# Tortoise_Board_schematic.net
KiCad netlist of a schematic drawn in EasyEDA
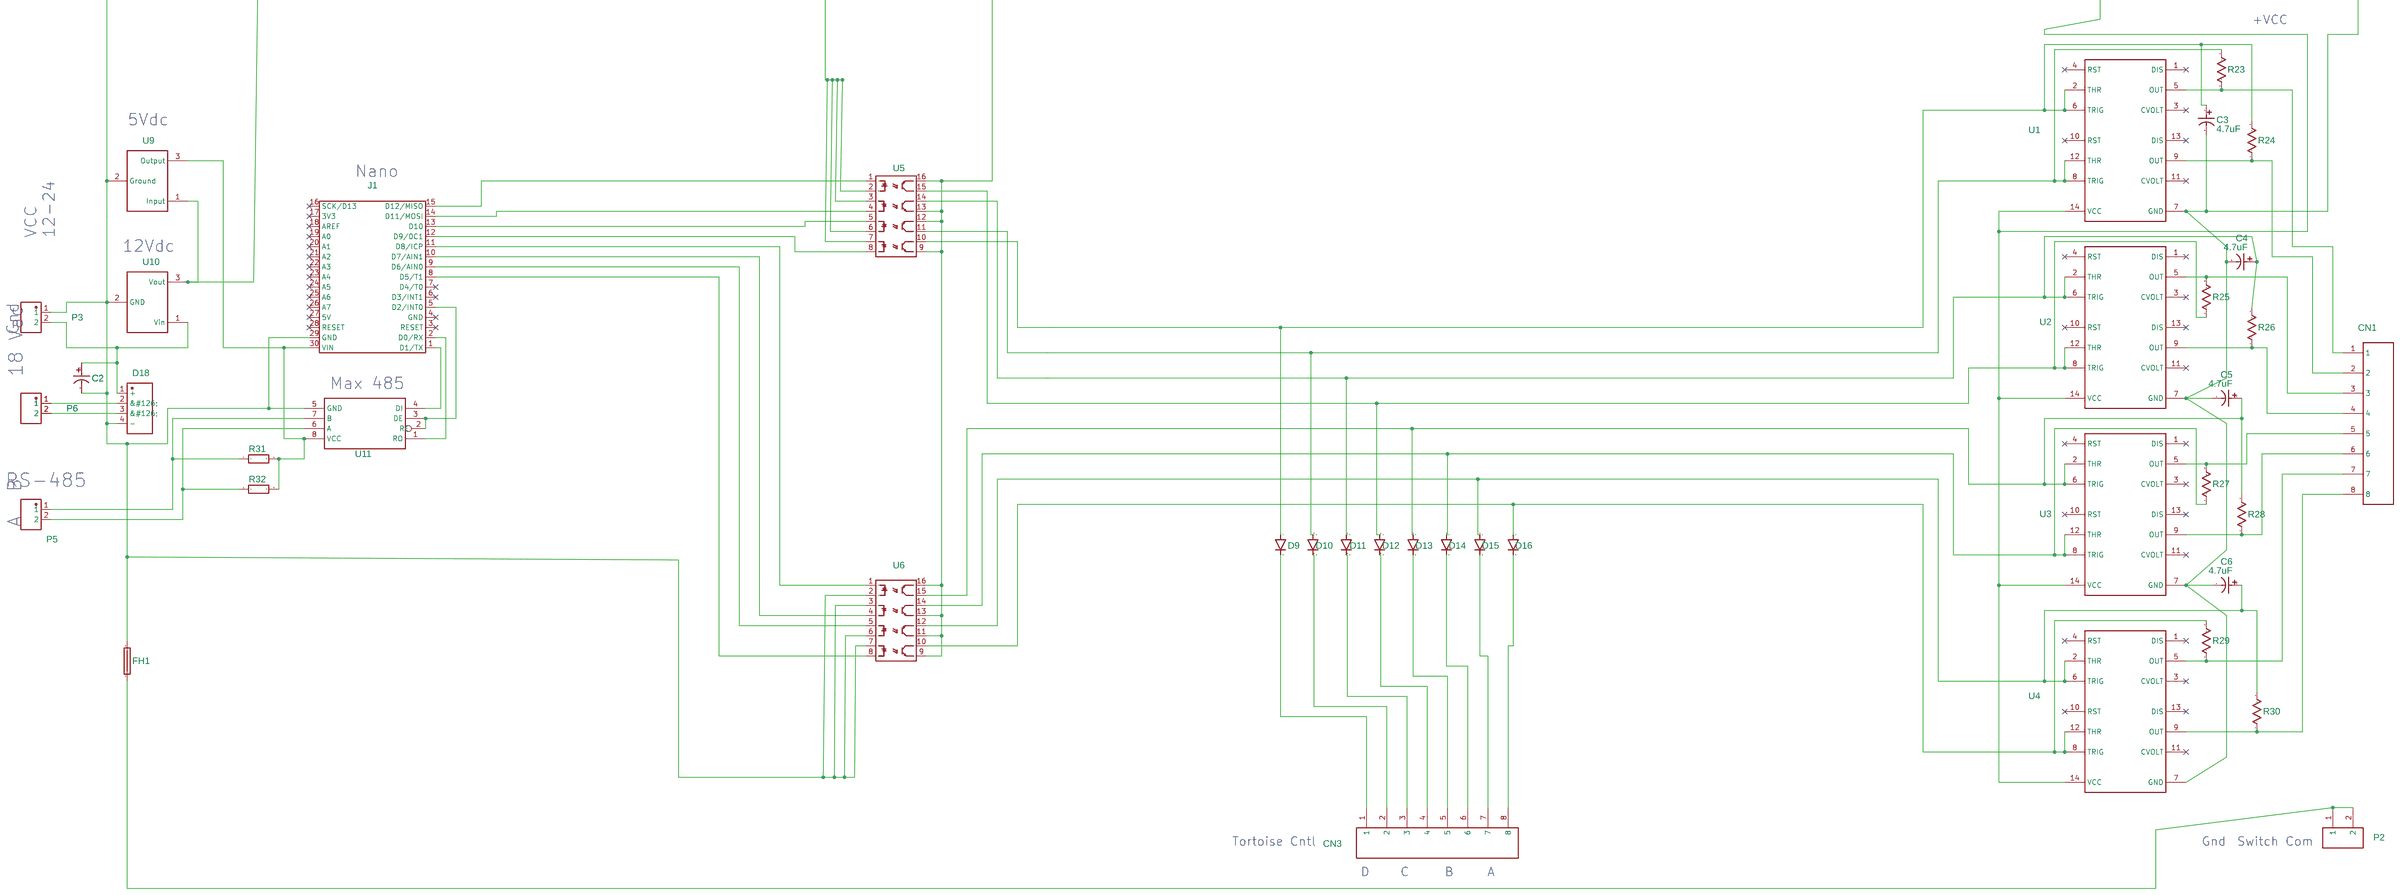
[diagram p0: schematic sheet]

(export (version "E")
  (design (tool "Eeschema 10.0.6"))
  (components
    (comp (ref "C2")
      (value "470uF")
      (fields
        (field (name "BOM_Manufacturer Part") "470uF 100V 16*25")
        (field (name "BOM_Supplier Part") "C72551")
      )
      (libsource (lib "") (part "470uF 100V 16*25"))
    )
    (comp (ref "C3")
      (value "4.7uF")
      (fields
        (field (name "BOM_Manufacturer Part") "4.7uF 50V 4*7")
        (field (name "BOM_Supplier Part") "C43841")
      )
      (libsource (lib "") (part "4.7uF 50V 4*7_1"))
    )
    (comp (ref "C4")
      (value "4.7uF")
      (fields
        (field (name "BOM_Manufacturer Part") "4.7uF 50V 4*7")
        (field (name "BOM_Supplier Part") "C43841")
      )
      (libsource (lib "") (part "4.7uF 50V 4*7"))
    )
    (comp (ref "C5")
      (value "4.7uF")
      (fields
        (field (name "BOM_Manufacturer Part") "4.7uF 50V 4*7")
        (field (name "BOM_Supplier Part") "C43841")
      )
      (libsource (lib "") (part "4.7uF 50V 4*7"))
    )
    (comp (ref "C6")
      (value "4.7uF")
      (fields
        (field (name "BOM_Manufacturer Part") "4.7uF 50V 4*7")
        (field (name "BOM_Supplier Part") "C43841")
      )
      (libsource (lib "") (part "4.7uF 50V 4*7"))
    )
    (comp (ref "CN1")
      (value "WJ25C-B-7.62-8P-13-00A")
      (fields (field (name "BOM_Supplier Part") "C49492"))
      (libsource (lib "") (part "Unknown_1845_850"))
    )
    (comp (ref "CN3")
      (value "WJ25C-B-7.62-8P-13-00A")
      (fields (field (name "BOM_Supplier Part") "C49492"))
      (libsource (lib "") (part "Unknown_930_1250"))
    )
    (comp (ref "D9")
      (value "DIODE")
      (fields (field (name "BOM_Manufacturer Part") "?"))
      (libsource (lib "") (part "Unknown_775_970"))
    )
    (comp (ref "D10")
      (value "DIODE")
      (fields (field (name "BOM_Manufacturer Part") "?"))
      (libsource (lib "") (part "Unknown_808_970"))
    )
    (comp (ref "D11")
      (value "DIODE")
      (fields (field (name "BOM_Manufacturer Part") "?"))
      (libsource (lib "") (part "Unknown_841_970"))
    )
    (comp (ref "D12")
      (value "DIODE")
      (fields (field (name "BOM_Manufacturer Part") "?"))
      (libsource (lib "") (part "Unknown_874_970"))
    )
    (comp (ref "D13")
      (value "DIODE")
      (fields (field (name "BOM_Manufacturer Part") "?"))
      (libsource (lib "") (part "Unknown_906_970"))
    )
    (comp (ref "D14")
      (value "DIODE")
      (fields (field (name "BOM_Manufacturer Part") "?"))
      (libsource (lib "") (part "Unknown_939_970"))
    )
    (comp (ref "D15")
      (value "DIODE")
      (fields (field (name "BOM_Manufacturer Part") "?"))
      (libsource (lib "") (part "Unknown_972_970"))
    )
    (comp (ref "D16")
      (value "DIODE")
      (fields (field (name "BOM_Manufacturer Part") "?"))
      (libsource (lib "") (part "Unknown_1005_970"))
    )
    (comp (ref "D18")
      (value "D50SB100")
      (fields (field (name "BOM_Supplier Part") "C411148"))
      (libsource (lib "") (part "Unknown_-360_835"))
    )
    (comp (ref "FH1")
      (value "64600001003")
      (fields (field (name "BOM_Supplier Part") "C206887"))
      (libsource (lib "") (part "Unknown_-365_1085"))
    )
    (comp (ref "J1") (value "Arduino_Nano_Header") (libsource (lib "") (part "Unknown_-125_705")))
    (comp (ref "P2")
      (value "WJ762-7.62-2P-13-00A")
      (fields (field (name "BOM_Supplier Part") "C72333"))
      (libsource (lib "") (part "Unknown_1825_1250"))
    )
    (comp (ref "P3")
      (value "WJ25C-B-2P")
      (fields (field (name "BOM_Supplier Part") "C8422"))
      (libsource (lib "") (part "Unknown_-460_745"))
    )
    (comp (ref "P5")
      (value "WJ25C-B-2P")
      (fields (field (name "BOM_Supplier Part") "C8422"))
      (libsource (lib "") (part "Unknown_-460_940"))
    )
    (comp (ref "P6")
      (value "WJ25C-B-2P")
      (fields (field (name "BOM_Supplier Part") "C8422"))
      (libsource (lib "") (part "Unknown_-460_835"))
    )
    (comp (ref "R23")
      (value "10k")
      (fields
        (field (name "BOM_Manufacturer Part") "RESISTOR_ALONG")
        (field (name "BOM_Supplier Part") "9339116")
      )
      (libsource (lib "") (part "Unknown_1705_500"))
    )
    (comp (ref "R24")
      (value "10k")
      (fields
        (field (name "BOM_Manufacturer Part") "RESISTOR_ALONG")
        (field (name "BOM_Supplier Part") "9339116")
      )
      (libsource (lib "") (part "Unknown_1735_570"))
    )
    (comp (ref "R25")
      (value "10k")
      (fields
        (field (name "BOM_Manufacturer Part") "RESISTOR_ALONG")
        (field (name "BOM_Supplier Part") "9339116")
      )
      (libsource (lib "") (part "Unknown_1690_725"))
    )
    (comp (ref "R26")
      (value "10k")
      (fields
        (field (name "BOM_Manufacturer Part") "RESISTOR_ALONG")
        (field (name "BOM_Supplier Part") "9339116")
      )
      (libsource (lib "") (part "Unknown_1735_755"))
    )
    (comp (ref "R27")
      (value "10k")
      (fields
        (field (name "BOM_Manufacturer Part") "RESISTOR_ALONG")
        (field (name "BOM_Supplier Part") "9339116")
      )
      (libsource (lib "") (part "Unknown_1690_910"))
    )
    (comp (ref "R28")
      (value "10k")
      (fields
        (field (name "BOM_Manufacturer Part") "RESISTOR_ALONG")
        (field (name "BOM_Supplier Part") "9339116")
      )
      (libsource (lib "") (part "Unknown_1725_940"))
    )
    (comp (ref "R29")
      (value "10k")
      (fields
        (field (name "BOM_Manufacturer Part") "RESISTOR_ALONG")
        (field (name "BOM_Supplier Part") "9339116")
      )
      (libsource (lib "") (part "Unknown_1690_1065"))
    )
    (comp (ref "R30")
      (value "10k")
      (fields
        (field (name "BOM_Manufacturer Part") "RESISTOR_ALONG")
        (field (name "BOM_Supplier Part") "9339116")
      )
      (libsource (lib "") (part "Unknown_1740_1135"))
    )
    (comp (ref "R31")
      (value "10K")
      (fields
        (field (name "BOM_Manufacturer Part") "CFR0W4J0103A50")
        (field (name "BOM_Supplier Part") "C61299")
      )
      (libsource (lib "") (part "CFR0W4J0103A50"))
    )
    (comp (ref "R32")
      (value "10K")
      (fields
        (field (name "BOM_Manufacturer Part") "CFR0W4J0103A50")
        (field (name "BOM_Supplier Part") "C61299")
      )
      (libsource (lib "") (part "CFR0W4J0103A50"))
    )
    (comp (ref "U1")
      (value "LM556CN")
      (fields (field (name "BOM_Manufacturer Part") "?"))
      (libsource (lib "") (part "Unknown_1610_570"))
    )
    (comp (ref "U2")
      (value "LM556CN")
      (fields (field (name "BOM_Manufacturer Part") "?"))
      (libsource (lib "") (part "Unknown_1610_755"))
    )
    (comp (ref "U3")
      (value "LM556CN")
      (fields (field (name "BOM_Manufacturer Part") "?"))
      (libsource (lib "") (part "Unknown_1610_940"))
    )
    (comp (ref "U4")
      (value "LM556CN")
      (fields (field (name "BOM_Manufacturer Part") "?"))
      (libsource (lib "") (part "Unknown_1610_1135"))
    )
    (comp (ref "U5")
      (value "Optocoupler_ILQ74 QUAD")
      (fields (field (name "BOM_Manufacturer Part") "?"))
      (libsource (lib "") (part "Unknown_395_645"))
    )
    (comp (ref "U6")
      (value "Optocoupler_ILQ74 QUAD")
      (fields (field (name "BOM_Manufacturer Part") "?"))
      (libsource (lib "") (part "Unknown_395_1045"))
    )
    (comp (ref "U9")
      (value "MC7805BTG")
      (fields (field (name "BOM_Supplier Part") "C45385"))
      (libsource (lib "") (part "Unknown_-345_610"))
    )
    (comp (ref "U10")
      (value "CJ7812")
      (fields (field (name "BOM_Supplier Part") "C77894"))
      (libsource (lib "") (part "Unknown_-345_730"))
    )
    (comp (ref "U11") (value "MAX485DIL") (libsource (lib "") (part "Unknown_-130_850")))
  )
  (nets
    (net (code "1") (name "Net-(C3-Pad1)") (class "Default")
      (node (ref "C3") (pin "1") (pinfunction "1_1") (pintype "input"))
      (node (ref "D9") (pin "A") (pinfunction "A_A") (pintype "unspecified"))
      (node (ref "R24") (pin "2") (pinfunction "2_2") (pintype "unspecified"))
      (node (ref "U1") (pin "2") (pinfunction "THR_2") (pintype "unspecified"))
      (node (ref "U1") (pin "6") (pinfunction "TRIG_6") (pintype "unspecified"))
      (node (ref "U5") (pin "10") (pinfunction "10_10") (pintype "unspecified"))
    )
    (net (code "2") (name "Net-(C4-Pad1)") (class "Default")
      (node (ref "C4") (pin "1") (pinfunction "1_1") (pintype "input"))
      (node (ref "D11") (pin "A") (pinfunction "A_A") (pintype "unspecified"))
      (node (ref "R26") (pin "2") (pinfunction "2_2") (pintype "unspecified"))
      (node (ref "U2") (pin "2") (pinfunction "THR_2") (pintype "unspecified"))
      (node (ref "U2") (pin "6") (pinfunction "TRIG_6") (pintype "unspecified"))
      (node (ref "U5") (pin "14") (pinfunction "14_14") (pintype "unspecified"))
    )
    (net (code "3") (name "Net-(C5-Pad1)") (class "Default")
      (node (ref "C5") (pin "1") (pinfunction "1_1") (pintype "input"))
      (node (ref "D13") (pin "A") (pinfunction "A_A") (pintype "unspecified"))
      (node (ref "R28") (pin "2") (pinfunction "2_2") (pintype "unspecified"))
      (node (ref "U3") (pin "2") (pinfunction "THR_2") (pintype "unspecified"))
      (node (ref "U3") (pin "6") (pinfunction "TRIG_6") (pintype "unspecified"))
      (node (ref "U6") (pin "15") (pinfunction "15_15") (pintype "unspecified"))
    )
    (net (code "4") (name "Net-(C6-Pad1)") (class "Default")
      (node (ref "C6") (pin "1") (pinfunction "1_1") (pintype "input"))
      (node (ref "D15") (pin "A") (pinfunction "A_A") (pintype "unspecified"))
      (node (ref "R30") (pin "2") (pinfunction "2_2") (pintype "unspecified"))
      (node (ref "U4") (pin "2") (pinfunction "THR_2") (pintype "unspecified"))
      (node (ref "U4") (pin "6") (pinfunction "TRIG_6") (pintype "unspecified"))
      (node (ref "U6") (pin "12") (pinfunction "12_12") (pintype "unspecified"))
    )
    (net (code "5") (name "Net-(CN1-Pad1)") (class "Default")
      (node (ref "CN1") (pin "1") (pinfunction "1_1") (pintype "input"))
      (node (ref "R23") (pin "1") (pinfunction "1_1") (pintype "unspecified"))
      (node (ref "U1") (pin "5") (pinfunction "OUT_5") (pintype "output"))
    )
    (net (code "6") (name "Net-(CN1-Pad2)") (class "Default")
      (node (ref "CN1") (pin "2") (pinfunction "2_2") (pintype "input"))
      (node (ref "R24") (pin "1") (pinfunction "1_1") (pintype "unspecified"))
      (node (ref "U1") (pin "9") (pinfunction "OUT_9") (pintype "output"))
    )
    (net (code "7") (name "Net-(CN1-Pad3)") (class "Default")
      (node (ref "CN1") (pin "3") (pinfunction "3_3") (pintype "input"))
      (node (ref "R25") (pin "2") (pinfunction "2_2") (pintype "unspecified"))
      (node (ref "U2") (pin "5") (pinfunction "OUT_5") (pintype "output"))
    )
    (net (code "8") (name "Net-(CN1-Pad4)") (class "Default")
      (node (ref "CN1") (pin "4") (pinfunction "4_4") (pintype "input"))
      (node (ref "R26") (pin "1") (pinfunction "1_1") (pintype "unspecified"))
      (node (ref "U2") (pin "9") (pinfunction "OUT_9") (pintype "output"))
    )
    (net (code "9") (name "Net-(CN1-Pad5)") (class "Default")
      (node (ref "CN1") (pin "5") (pinfunction "5_5") (pintype "input"))
      (node (ref "R27") (pin "2") (pinfunction "2_2") (pintype "unspecified"))
      (node (ref "U3") (pin "5") (pinfunction "OUT_5") (pintype "output"))
    )
    (net (code "10") (name "Net-(CN1-Pad6)") (class "Default")
      (node (ref "CN1") (pin "6") (pinfunction "6_6") (pintype "input"))
      (node (ref "R28") (pin "1") (pinfunction "1_1") (pintype "unspecified"))
      (node (ref "U3") (pin "9") (pinfunction "OUT_9") (pintype "output"))
    )
    (net (code "11") (name "Net-(CN1-Pad7)") (class "Default")
      (node (ref "CN1") (pin "7") (pinfunction "7_7") (pintype "input"))
      (node (ref "R29") (pin "1") (pinfunction "1_1") (pintype "unspecified"))
      (node (ref "U4") (pin "5") (pinfunction "OUT_5") (pintype "output"))
    )
    (net (code "12") (name "Net-(CN1-Pad8)") (class "Default")
      (node (ref "CN1") (pin "8") (pinfunction "8_8") (pintype "input"))
      (node (ref "R30") (pin "1") (pinfunction "1_1") (pintype "unspecified"))
      (node (ref "U4") (pin "9") (pinfunction "OUT_9") (pintype "output"))
    )
    (net (code "13") (name "Net-(CN3-Pad1)") (class "Default")
      (node (ref "CN3") (pin "1") (pinfunction "1_1") (pintype "input"))
      (node (ref "D9") (pin "C") (pinfunction "C_C") (pintype "unspecified"))
    )
    (net (code "14") (name "Net-(CN3-Pad2)") (class "Default")
      (node (ref "CN3") (pin "2") (pinfunction "2_2") (pintype "input"))
      (node (ref "D10") (pin "C") (pinfunction "C_C") (pintype "unspecified"))
    )
    (net (code "15") (name "Net-(CN3-Pad3)") (class "Default")
      (node (ref "CN3") (pin "3") (pinfunction "3_3") (pintype "input"))
      (node (ref "D11") (pin "C") (pinfunction "C_C") (pintype "unspecified"))
    )
    (net (code "16") (name "Net-(CN3-Pad4)") (class "Default")
      (node (ref "CN3") (pin "4") (pinfunction "4_4") (pintype "input"))
      (node (ref "D12") (pin "C") (pinfunction "C_C") (pintype "unspecified"))
    )
    (net (code "17") (name "Net-(CN3-Pad5)") (class "Default")
      (node (ref "CN3") (pin "5") (pinfunction "5_5") (pintype "input"))
      (node (ref "D13") (pin "C") (pinfunction "C_C") (pintype "unspecified"))
    )
    (net (code "18") (name "Net-(CN3-Pad6)") (class "Default")
      (node (ref "CN3") (pin "6") (pinfunction "6_6") (pintype "input"))
      (node (ref "D14") (pin "C") (pinfunction "C_C") (pintype "unspecified"))
    )
    (net (code "19") (name "Net-(CN3-Pad7)") (class "Default")
      (node (ref "CN3") (pin "7") (pinfunction "7_7") (pintype "input"))
      (node (ref "D15") (pin "C") (pinfunction "C_C") (pintype "unspecified"))
    )
    (net (code "20") (name "Net-(CN3-Pad8)") (class "Default")
      (node (ref "CN3") (pin "8") (pinfunction "8_8") (pintype "input"))
      (node (ref "D16") (pin "C") (pinfunction "C_C") (pintype "unspecified"))
    )
    (net (code "21") (name "Net-(D10-PadA)") (class "Default")
      (node (ref "D10") (pin "A") (pinfunction "A_A") (pintype "unspecified"))
      (node (ref "R23") (pin "2") (pinfunction "2_2") (pintype "unspecified"))
      (node (ref "U1") (pin "12") (pinfunction "THR_12") (pintype "unspecified"))
      (node (ref "U1") (pin "8") (pinfunction "TRIG_8") (pintype "unspecified"))
      (node (ref "U5") (pin "11") (pinfunction "11_11") (pintype "unspecified"))
    )
    (net (code "22") (name "Net-(D12-PadA)") (class "Default")
      (node (ref "D12") (pin "A") (pinfunction "A_A") (pintype "unspecified"))
      (node (ref "R25") (pin "1") (pinfunction "1_1") (pintype "unspecified"))
      (node (ref "U2") (pin "12") (pinfunction "THR_12") (pintype "unspecified"))
      (node (ref "U2") (pin "8") (pinfunction "TRIG_8") (pintype "unspecified"))
      (node (ref "U5") (pin "15") (pinfunction "15_15") (pintype "unspecified"))
    )
    (net (code "23") (name "Net-(D14-PadA)") (class "Default")
      (node (ref "D14") (pin "A") (pinfunction "A_A") (pintype "unspecified"))
      (node (ref "R27") (pin "1") (pinfunction "1_1") (pintype "unspecified"))
      (node (ref "U3") (pin "12") (pinfunction "THR_12") (pintype "unspecified"))
      (node (ref "U3") (pin "8") (pinfunction "TRIG_8") (pintype "unspecified"))
      (node (ref "U6") (pin "14") (pinfunction "14_14") (pintype "unspecified"))
    )
    (net (code "24") (name "Net-(D16-PadA)") (class "Default")
      (node (ref "D16") (pin "A") (pinfunction "A_A") (pintype "unspecified"))
      (node (ref "R29") (pin "2") (pinfunction "2_2") (pintype "unspecified"))
      (node (ref "U4") (pin "12") (pinfunction "THR_12") (pintype "unspecified"))
      (node (ref "U4") (pin "8") (pinfunction "TRIG_8") (pintype "unspecified"))
      (node (ref "U6") (pin "10") (pinfunction "10_10") (pintype "unspecified"))
    )
    (net (code "25") (name "Net-(D18-&#126;-Pad2)") (class "Default")
      (node (ref "D18") (pin "2") (pinfunction "&#126;_2") (pintype "unspecified"))
      (node (ref "P6") (pin "1") (pinfunction "1_1") (pintype "unspecified"))
    )
    (net (code "26") (name "Net-(D18-&#126;-Pad3)") (class "Default")
      (node (ref "D18") (pin "3") (pinfunction "&#126;_3") (pintype "unspecified"))
      (node (ref "P6") (pin "2") (pinfunction "2_2") (pintype "unspecified"))
    )
    (net (code "27") (name "Net-(D18-+)") (class "Default")
      (node (ref "C2") (pin "1") (pinfunction "1_1") (pintype "input"))
      (node (ref "D18") (pin "1") (pinfunction "+_1") (pintype "unspecified"))
      (node (ref "P3") (pin "2") (pinfunction "2_2") (pintype "unspecified"))
      (node (ref "U10") (pin "1") (pinfunction "Vin_1") (pintype "unspecified"))
    )
    (net (code "28") (name "Net-(D18--)") (class "Default")
      (node (ref "C2") (pin "2") (pinfunction "2_2") (pintype "input"))
      (node (ref "C3") (pin "2") (pinfunction "2_2") (pintype "input"))
      (node (ref "C4") (pin "2") (pinfunction "2_2") (pintype "input"))
      (node (ref "C5") (pin "2") (pinfunction "2_2") (pintype "input"))
      (node (ref "C6") (pin "2") (pinfunction "2_2") (pintype "input"))
      (node (ref "D18") (pin "4") (pinfunction "-_4") (pintype "unspecified"))
      (node (ref "FH1") (pin "2") (pinfunction "2_2") (pintype "unspecified"))
      (node (ref "J1") (pin "29") (pinfunction "GND_29") (pintype "unspecified"))
      (node (ref "P3") (pin "1") (pinfunction "1_1") (pintype "unspecified"))
      (node (ref "U1") (pin "7") (pinfunction "GND_7") (pintype "passive"))
      (node (ref "U10") (pin "2") (pinfunction "GND_2") (pintype "unspecified"))
      (node (ref "U11") (pin "5") (pinfunction "GND_5") (pintype "unspecified"))
      (node (ref "U2") (pin "7") (pinfunction "GND_7") (pintype "passive"))
      (node (ref "U3") (pin "7") (pinfunction "GND_7") (pintype "passive"))
      (node (ref "U4") (pin "7") (pinfunction "GND_7") (pintype "passive"))
      (node (ref "U5") (pin "12") (pinfunction "12_12") (pintype "unspecified"))
      (node (ref "U5") (pin "13") (pinfunction "13_13") (pintype "unspecified"))
      (node (ref "U5") (pin "16") (pinfunction "16_16") (pintype "unspecified"))
      (node (ref "U5") (pin "2") (pinfunction "2_2") (pintype "unspecified"))
      (node (ref "U5") (pin "3") (pinfunction "3_3") (pintype "unspecified"))
      (node (ref "U5") (pin "6") (pinfunction "6_6") (pintype "unspecified"))
      (node (ref "U5") (pin "7") (pinfunction "7_7") (pintype "unspecified"))
      (node (ref "U5") (pin "9") (pinfunction "9_9") (pintype "unspecified"))
      (node (ref "U6") (pin "11") (pinfunction "11_11") (pintype "unspecified"))
      (node (ref "U6") (pin "13") (pinfunction "13_13") (pintype "unspecified"))
      (node (ref "U6") (pin "16") (pinfunction "16_16") (pintype "unspecified"))
      (node (ref "U6") (pin "2") (pinfunction "2_2") (pintype "unspecified"))
      (node (ref "U6") (pin "3") (pinfunction "3_3") (pintype "unspecified"))
      (node (ref "U6") (pin "6") (pinfunction "6_6") (pintype "unspecified"))
      (node (ref "U6") (pin "7") (pinfunction "7_7") (pintype "unspecified"))
      (node (ref "U6") (pin "9") (pinfunction "9_9") (pintype "unspecified"))
      (node (ref "U9") (pin "2") (pinfunction "Ground_2") (pintype "unspecified"))
    )
    (net (code "29") (name "Net-(FH1-Pad1)") (class "Default")
      (node (ref "FH1") (pin "1") (pinfunction "1_1") (pintype "unspecified"))
      (node (ref "P2") (pin "1") (pinfunction "1_1") (pintype "unspecified"))
      (node (ref "P2") (pin "2") (pinfunction "2_2") (pintype "unspecified"))
    )
    (net (code "30") (name "Net-(J1-D0{slash}RX)") (class "Default")
      (node (ref "J1") (pin "2") (pinfunction "D0/RX_2") (pintype "unspecified"))
      (node (ref "U11") (pin "1") (pinfunction "RO_1") (pintype "unspecified"))
    )
    (net (code "31") (name "Net-(J1-D1{slash}TX)") (class "Default")
      (node (ref "J1") (pin "1") (pinfunction "D1/TX_1") (pintype "unspecified"))
      (node (ref "U11") (pin "4") (pinfunction "DI_4") (pintype "unspecified"))
    )
    (net (code "32") (name "Net-(J1-D2{slash}INT0)") (class "Default")
      (node (ref "J1") (pin "5") (pinfunction "D2/INT0_5") (pintype "unspecified"))
      (node (ref "U11") (pin "2") (pinfunction "RE_2") (pintype "unspecified"))
      (node (ref "U11") (pin "3") (pinfunction "DE_3") (pintype "unspecified"))
    )
    (net (code "33") (name "Net-(J1-D5{slash}T1)") (class "Default")
      (node (ref "J1") (pin "8") (pinfunction "D5/T1_8") (pintype "unspecified"))
      (node (ref "U6") (pin "8") (pinfunction "8_8") (pintype "unspecified"))
    )
    (net (code "34") (name "Net-(J1-D6{slash}AIN0)") (class "Default")
      (node (ref "J1") (pin "9") (pinfunction "D6/AIN0_9") (pintype "unspecified"))
      (node (ref "U6") (pin "5") (pinfunction "5_5") (pintype "unspecified"))
    )
    (net (code "35") (name "Net-(J1-D7{slash}AIN1)") (class "Default")
      (node (ref "J1") (pin "10") (pinfunction "D7/AIN1_10") (pintype "unspecified"))
      (node (ref "U6") (pin "4") (pinfunction "4_4") (pintype "unspecified"))
    )
    (net (code "36") (name "Net-(J1-D8{slash}ICP)") (class "Default")
      (node (ref "J1") (pin "11") (pinfunction "D8/ICP_11") (pintype "unspecified"))
      (node (ref "U6") (pin "1") (pinfunction "1_1") (pintype "unspecified"))
    )
    (net (code "37") (name "Net-(J1-D9{slash}0C1)") (class "Default")
      (node (ref "J1") (pin "12") (pinfunction "D9/0C1_12") (pintype "unspecified"))
      (node (ref "U5") (pin "8") (pinfunction "8_8") (pintype "unspecified"))
    )
    (net (code "38") (name "Net-(J1-D10)") (class "Default")
      (node (ref "J1") (pin "13") (pinfunction "D10_13") (pintype "unspecified"))
      (node (ref "U5") (pin "5") (pinfunction "5_5") (pintype "unspecified"))
    )
    (net (code "39") (name "Net-(J1-D11{slash}MOSI)") (class "Default")
      (node (ref "J1") (pin "14") (pinfunction "D11/MOSI_14") (pintype "unspecified"))
      (node (ref "U5") (pin "4") (pinfunction "4_4") (pintype "unspecified"))
    )
    (net (code "40") (name "Net-(J1-D12{slash}MISO)") (class "Default")
      (node (ref "J1") (pin "15") (pinfunction "D12/MISO_15") (pintype "unspecified"))
      (node (ref "U5") (pin "1") (pinfunction "1_1") (pintype "unspecified"))
    )
    (net (code "41") (name "Net-(J1-VIN)") (class "Default")
      (node (ref "J1") (pin "30") (pinfunction "VIN_30") (pintype "unspecified"))
      (node (ref "R31") (pin "2") (pinfunction "2_2") (pintype "input"))
      (node (ref "R32") (pin "2") (pinfunction "2_2") (pintype "input"))
      (node (ref "U11") (pin "8") (pinfunction "VCC_8") (pintype "unspecified"))
      (node (ref "U9") (pin "3") (pinfunction "Output_3") (pintype "unspecified"))
    )
    (net (code "42") (name "Net-(U1-VCC)") (class "Default")
      (node (ref "U1") (pin "14") (pinfunction "VCC_14") (pintype "passive"))
      (node (ref "U10") (pin "3") (pinfunction "Vout_3") (pintype "unspecified"))
      (node (ref "U2") (pin "14") (pinfunction "VCC_14") (pintype "passive"))
      (node (ref "U3") (pin "14") (pinfunction "VCC_14") (pintype "passive"))
      (node (ref "U4") (pin "14") (pinfunction "VCC_14") (pintype "passive"))
      (node (ref "U9") (pin "1") (pinfunction "Input_1") (pintype "unspecified"))
    )
    (net (code "43") (name "Net-(U11-A)") (class "Default")
      (node (ref "P5") (pin "2") (pinfunction "2_2") (pintype "unspecified"))
      (node (ref "R32") (pin "1") (pinfunction "1_1") (pintype "input"))
      (node (ref "U11") (pin "6") (pinfunction "A_6") (pintype "unspecified"))
    )
    (net (code "44") (name "Net-(U11-B)") (class "Default")
      (node (ref "P5") (pin "1") (pinfunction "1_1") (pintype "unspecified"))
      (node (ref "R31") (pin "1") (pinfunction "1_1") (pintype "input"))
      (node (ref "U11") (pin "7") (pinfunction "B_7") (pintype "unspecified"))
    )
    (net (code "45") (name "unconnected-(J1-3V3-Pad17)") (class "Default")
      (node (ref "J1") (pin "17") (pinfunction "3V3_17") (pintype "unspecified+no_connect"))
    )
    (net (code "46") (name "unconnected-(J1-5V-Pad27)") (class "Default")
      (node (ref "J1") (pin "27") (pinfunction "5V_27") (pintype "unspecified+no_connect"))
    )
    (net (code "47") (name "unconnected-(J1-A0-Pad19)") (class "Default")
      (node (ref "J1") (pin "19") (pinfunction "A0_19") (pintype "unspecified+no_connect"))
    )
    (net (code "48") (name "unconnected-(J1-A1-Pad20)") (class "Default")
      (node (ref "J1") (pin "20") (pinfunction "A1_20") (pintype "unspecified+no_connect"))
    )
    (net (code "49") (name "unconnected-(J1-A2-Pad21)") (class "Default")
      (node (ref "J1") (pin "21") (pinfunction "A2_21") (pintype "unspecified+no_connect"))
    )
    (net (code "50") (name "unconnected-(J1-A3-Pad22)") (class "Default")
      (node (ref "J1") (pin "22") (pinfunction "A3_22") (pintype "unspecified+no_connect"))
    )
    (net (code "51") (name "unconnected-(J1-A4-Pad23)") (class "Default")
      (node (ref "J1") (pin "23") (pinfunction "A4_23") (pintype "unspecified+no_connect"))
    )
    (net (code "52") (name "unconnected-(J1-A5-Pad24)") (class "Default")
      (node (ref "J1") (pin "24") (pinfunction "A5_24") (pintype "unspecified+no_connect"))
    )
    (net (code "53") (name "unconnected-(J1-A6-Pad25)") (class "Default")
      (node (ref "J1") (pin "25") (pinfunction "A6_25") (pintype "unspecified+no_connect"))
    )
    (net (code "54") (name "unconnected-(J1-A7-Pad26)") (class "Default")
      (node (ref "J1") (pin "26") (pinfunction "A7_26") (pintype "unspecified+no_connect"))
    )
    (net (code "55") (name "unconnected-(J1-AREF-Pad18)") (class "Default")
      (node (ref "J1") (pin "18") (pinfunction "AREF_18") (pintype "unspecified+no_connect"))
    )
    (net (code "56") (name "unconnected-(J1-D3{slash}INT1-Pad6)") (class "Default")
      (node (ref "J1") (pin "6") (pinfunction "D3/INT1_6") (pintype "unspecified+no_connect"))
    )
    (net (code "57") (name "unconnected-(J1-D4{slash}T0-Pad7)") (class "Default")
      (node (ref "J1") (pin "7") (pinfunction "D4/T0_7") (pintype "unspecified+no_connect"))
    )
    (net (code "58") (name "unconnected-(J1-GND-Pad4)") (class "Default")
      (node (ref "J1") (pin "4") (pinfunction "GND_4") (pintype "unspecified+no_connect"))
    )
    (net (code "59") (name "unconnected-(J1-RESET-Pad3)") (class "Default")
      (node (ref "J1") (pin "3") (pinfunction "RESET_3") (pintype "unspecified+no_connect"))
    )
    (net (code "60") (name "unconnected-(J1-RESET-Pad28)") (class "Default")
      (node (ref "J1") (pin "28") (pinfunction "RESET_28") (pintype "unspecified+no_connect"))
    )
    (net (code "61") (name "unconnected-(J1-SCK{slash}D13-Pad16)") (class "Default")
      (node (ref "J1") (pin "16") (pinfunction "SCK/D13_16") (pintype "unspecified+no_connect"))
    )
    (net (code "62") (name "unconnected-(U1-CVOLT-Pad3)") (class "Default")
      (node (ref "U1") (pin "3") (pinfunction "CVOLT_3") (pintype "unspecified+no_connect"))
    )
    (net (code "63") (name "unconnected-(U1-CVOLT-Pad11)") (class "Default")
      (node (ref "U1") (pin "11") (pinfunction "CVOLT_11") (pintype "unspecified+no_connect"))
    )
    (net (code "64") (name "unconnected-(U1-DIS-Pad1)") (class "Default")
      (node (ref "U1") (pin "1") (pinfunction "DIS_1") (pintype "unspecified+no_connect"))
    )
    (net (code "65") (name "unconnected-(U1-DIS-Pad13)") (class "Default")
      (node (ref "U1") (pin "13") (pinfunction "DIS_13") (pintype "unspecified+no_connect"))
    )
    (net (code "66") (name "unconnected-(U1-RST-Pad4)") (class "Default")
      (node (ref "U1") (pin "4") (pinfunction "RST_4") (pintype "unspecified+no_connect"))
    )
    (net (code "67") (name "unconnected-(U1-RST-Pad10)") (class "Default")
      (node (ref "U1") (pin "10") (pinfunction "RST_10") (pintype "unspecified+no_connect"))
    )
    (net (code "68") (name "unconnected-(U2-CVOLT-Pad3)") (class "Default")
      (node (ref "U2") (pin "3") (pinfunction "CVOLT_3") (pintype "unspecified+no_connect"))
    )
    (net (code "69") (name "unconnected-(U2-CVOLT-Pad11)") (class "Default")
      (node (ref "U2") (pin "11") (pinfunction "CVOLT_11") (pintype "unspecified+no_connect"))
    )
    (net (code "70") (name "unconnected-(U2-DIS-Pad1)") (class "Default")
      (node (ref "U2") (pin "1") (pinfunction "DIS_1") (pintype "unspecified+no_connect"))
    )
    (net (code "71") (name "unconnected-(U2-DIS-Pad13)") (class "Default")
      (node (ref "U2") (pin "13") (pinfunction "DIS_13") (pintype "unspecified+no_connect"))
    )
    (net (code "72") (name "unconnected-(U2-RST-Pad4)") (class "Default")
      (node (ref "U2") (pin "4") (pinfunction "RST_4") (pintype "unspecified+no_connect"))
    )
    (net (code "73") (name "unconnected-(U2-RST-Pad10)") (class "Default")
      (node (ref "U2") (pin "10") (pinfunction "RST_10") (pintype "unspecified+no_connect"))
    )
    (net (code "74") (name "unconnected-(U3-CVOLT-Pad3)") (class "Default")
      (node (ref "U3") (pin "3") (pinfunction "CVOLT_3") (pintype "unspecified+no_connect"))
    )
    (net (code "75") (name "unconnected-(U3-CVOLT-Pad11)") (class "Default")
      (node (ref "U3") (pin "11") (pinfunction "CVOLT_11") (pintype "unspecified+no_connect"))
    )
    (net (code "76") (name "unconnected-(U3-DIS-Pad1)") (class "Default")
      (node (ref "U3") (pin "1") (pinfunction "DIS_1") (pintype "unspecified+no_connect"))
    )
    (net (code "77") (name "unconnected-(U3-DIS-Pad13)") (class "Default")
      (node (ref "U3") (pin "13") (pinfunction "DIS_13") (pintype "unspecified+no_connect"))
    )
    (net (code "78") (name "unconnected-(U3-RST-Pad4)") (class "Default")
      (node (ref "U3") (pin "4") (pinfunction "RST_4") (pintype "unspecified+no_connect"))
    )
    (net (code "79") (name "unconnected-(U3-RST-Pad10)") (class "Default")
      (node (ref "U3") (pin "10") (pinfunction "RST_10") (pintype "unspecified+no_connect"))
    )
    (net (code "80") (name "unconnected-(U4-CVOLT-Pad3)") (class "Default")
      (node (ref "U4") (pin "3") (pinfunction "CVOLT_3") (pintype "unspecified+no_connect"))
    )
    (net (code "81") (name "unconnected-(U4-CVOLT-Pad11)") (class "Default")
      (node (ref "U4") (pin "11") (pinfunction "CVOLT_11") (pintype "unspecified+no_connect"))
    )
    (net (code "82") (name "unconnected-(U4-DIS-Pad1)") (class "Default")
      (node (ref "U4") (pin "1") (pinfunction "DIS_1") (pintype "unspecified+no_connect"))
    )
    (net (code "83") (name "unconnected-(U4-DIS-Pad13)") (class "Default")
      (node (ref "U4") (pin "13") (pinfunction "DIS_13") (pintype "unspecified+no_connect"))
    )
    (net (code "84") (name "unconnected-(U4-RST-Pad4)") (class "Default")
      (node (ref "U4") (pin "4") (pinfunction "RST_4") (pintype "unspecified+no_connect"))
    )
    (net (code "85") (name "unconnected-(U4-RST-Pad10)") (class "Default")
      (node (ref "U4") (pin "10") (pinfunction "RST_10") (pintype "unspecified+no_connect"))
    )
  )
)
